# ElectricalLoads.net
KiCad netlist of a schematic drawn in EAGLE
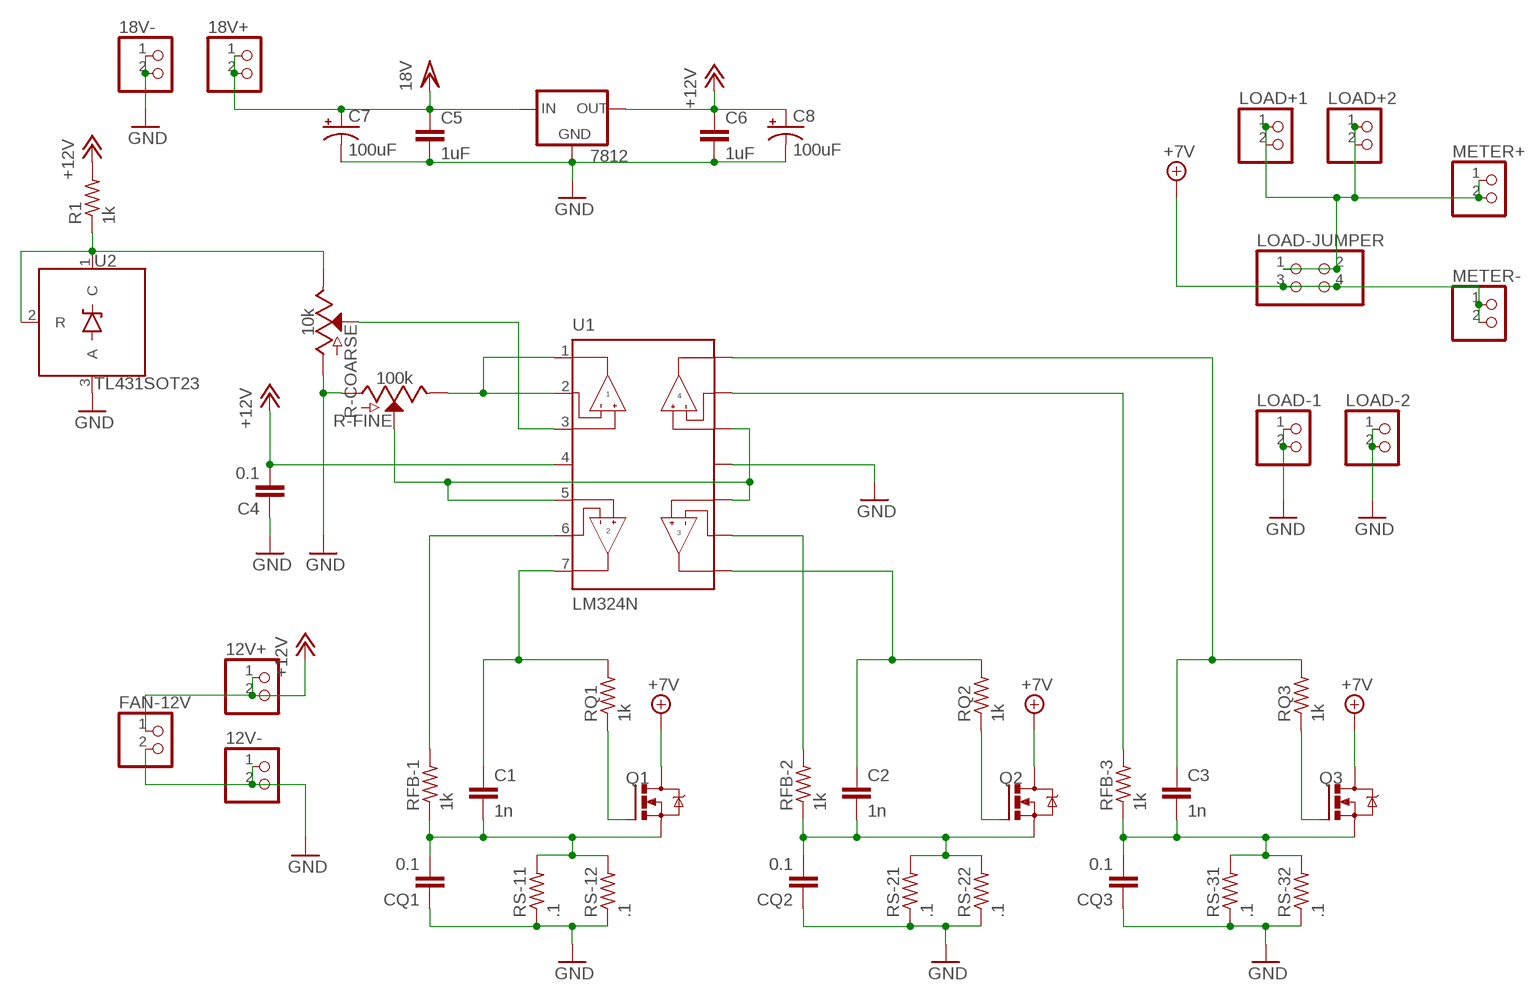
[diagram p0: schematic, sheet 1]

(export (version "E")
  (design (tool "Eeschema 10.0.6"))
  (components
    (comp (ref "12V+")
      (value "PINHD-1X2")
      (footprint "eagle-import:1X02")
      (libsource (lib "eagle-import") (part "PINHD-1X2"))
    )
    (comp (ref "12V-")
      (value "PINHD-1X2")
      (footprint "eagle-import:1X02")
      (libsource (lib "eagle-import") (part "PINHD-1X2"))
    )
    (comp (ref "18V+")
      (value "PINHD-1X2")
      (footprint "eagle-import:1X02")
      (libsource (lib "eagle-import") (part "PINHD-1X2"))
    )
    (comp (ref "18V-")
      (value "PINHD-1X2")
      (footprint "eagle-import:1X02")
      (libsource (lib "eagle-import") (part "PINHD-1X2"))
    )
    (comp (ref "7812")
      (value "V_REG_78XX-TO-220")
      (footprint "eagle-import:TO-220-ALT")
      (libsource (lib "eagle-import") (part "V_REG_78XX-TO-220"))
    )
    (comp (ref "C1")
      (value "1n")
      (footprint "eagle-import:0805")
      (libsource (lib "eagle-import") (part "CAP-0805"))
    )
    (comp (ref "C2")
      (value "1n")
      (footprint "eagle-import:0805")
      (libsource (lib "eagle-import") (part "CAP-0805"))
    )
    (comp (ref "C3")
      (value "1n")
      (footprint "eagle-import:0805")
      (libsource (lib "eagle-import") (part "CAP-0805"))
    )
    (comp (ref "C4")
      (value "0.1")
      (footprint "eagle-import:0805")
      (libsource (lib "eagle-import") (part "CAP-0805"))
    )
    (comp (ref "C5")
      (value "1uF")
      (footprint "eagle-import:1210")
      (libsource (lib "eagle-import") (part "10UF-1210-50V-20%"))
    )
    (comp (ref "C6")
      (value "1uF")
      (footprint "eagle-import:1210")
      (libsource (lib "eagle-import") (part "10UF-1210-50V-20%"))
    )
    (comp (ref "C7")
      (value "100uF")
      (footprint "eagle-import:PANASONIC_D")
      (libsource (lib "eagle-import") (part "100UF-POLAR-25V-20%(ELEC)"))
    )
    (comp (ref "C8")
      (value "100uF")
      (footprint "eagle-import:PANASONIC_D")
      (libsource (lib "eagle-import") (part "100UF-POLAR-25V-20%(ELEC)"))
    )
    (comp (ref "CQ1")
      (value "0.1")
      (footprint "eagle-import:0805")
      (libsource (lib "eagle-import") (part "CAP-0805"))
    )
    (comp (ref "CQ2")
      (value "0.1")
      (footprint "eagle-import:0805")
      (libsource (lib "eagle-import") (part "CAP-0805"))
    )
    (comp (ref "CQ3")
      (value "0.1")
      (footprint "eagle-import:0805")
      (libsource (lib "eagle-import") (part "CAP-0805"))
    )
    (comp (ref "FAN-12V")
      (value "PINHD-1X2")
      (footprint "eagle-import:1X02")
      (libsource (lib "eagle-import") (part "PINHD-1X2"))
    )
    (comp (ref "LOAD+1")
      (value "PINHD-1X2")
      (footprint "eagle-import:1X02")
      (libsource (lib "eagle-import") (part "PINHD-1X2"))
    )
    (comp (ref "LOAD+2")
      (value "PINHD-1X2")
      (footprint "eagle-import:1X02")
      (libsource (lib "eagle-import") (part "PINHD-1X2"))
    )
    (comp (ref "LOAD-1")
      (value "PINHD-1X2")
      (footprint "eagle-import:1X02")
      (libsource (lib "eagle-import") (part "PINHD-1X2"))
    )
    (comp (ref "LOAD-2")
      (value "PINHD-1X2")
      (footprint "eagle-import:1X02")
      (libsource (lib "eagle-import") (part "PINHD-1X2"))
    )
    (comp (ref "LOAD-JUMPER")
      (value "PINHD-2X2")
      (footprint "eagle-import:2X02")
      (libsource (lib "eagle-import") (part "PINHD-2X2"))
    )
    (comp (ref "METER+")
      (value "PINHD-1X2")
      (footprint "eagle-import:1X02")
      (libsource (lib "eagle-import") (part "PINHD-1X2"))
    )
    (comp (ref "METER-")
      (value "PINHD-1X2")
      (footprint "eagle-import:1X02")
      (libsource (lib "eagle-import") (part "PINHD-1X2"))
    )
    (comp (ref "Q1")
      (value "IRLZ44Z")
      (footprint "eagle-import:TO220BH")
      (libsource (lib "eagle-import") (part "IRLZ44Z"))
    )
    (comp (ref "Q2")
      (value "IRLZ44Z")
      (footprint "eagle-import:TO220BH")
      (libsource (lib "eagle-import") (part "IRLZ44Z"))
    )
    (comp (ref "Q3")
      (value "IRLZ44Z")
      (footprint "eagle-import:TO220BH")
      (libsource (lib "eagle-import") (part "IRLZ44Z"))
    )
    (comp (ref "R-COARSE")
      (value "10k")
      (footprint "eagle-import:POT-PTH-ALPS")
      (libsource (lib "eagle-import") (part "POTENTIOMETER-PTH-9MM-1/20W-20%"))
    )
    (comp (ref "R-FINE")
      (value "100k")
      (footprint "eagle-import:POT-PTH-ALPS")
      (libsource (lib "eagle-import") (part "POTENTIOMETER-PTH-9MM-1/20W-20%"))
    )
    (comp (ref "R1")
      (value "1k")
      (footprint "eagle-import:M0805")
      (libsource (lib "eagle-import") (part "R-US_M0805"))
    )
    (comp (ref "RFB-1")
      (value "1k")
      (footprint "eagle-import:M0805")
      (libsource (lib "eagle-import") (part "R-US_M0805"))
    )
    (comp (ref "RFB-2")
      (value "1k")
      (footprint "eagle-import:M0805")
      (libsource (lib "eagle-import") (part "R-US_M0805"))
    )
    (comp (ref "RFB-3")
      (value "1k")
      (footprint "eagle-import:M0805")
      (libsource (lib "eagle-import") (part "R-US_M0805"))
    )
    (comp (ref "RQ1")
      (value "1k")
      (footprint "eagle-import:M0805")
      (libsource (lib "eagle-import") (part "R-US_M0805"))
    )
    (comp (ref "RQ2")
      (value "1k")
      (footprint "eagle-import:M0805")
      (libsource (lib "eagle-import") (part "R-US_M0805"))
    )
    (comp (ref "RQ3")
      (value "1k")
      (footprint "eagle-import:M0805")
      (libsource (lib "eagle-import") (part "R-US_M0805"))
    )
    (comp (ref "RS-11")
      (value ".1")
      (footprint "eagle-import:M1206")
      (libsource (lib "eagle-import") (part "R-US_M1206"))
    )
    (comp (ref "RS-12")
      (value ".1")
      (footprint "eagle-import:M1206")
      (libsource (lib "eagle-import") (part "R-US_M1206"))
    )
    (comp (ref "RS-21")
      (value ".1")
      (footprint "eagle-import:M1206")
      (libsource (lib "eagle-import") (part "R-US_M1206"))
    )
    (comp (ref "RS-22")
      (value ".1")
      (footprint "eagle-import:M1206")
      (libsource (lib "eagle-import") (part "R-US_M1206"))
    )
    (comp (ref "RS-31")
      (value ".1")
      (footprint "eagle-import:M1206")
      (libsource (lib "eagle-import") (part "R-US_M1206"))
    )
    (comp (ref "RS-32")
      (value ".1")
      (footprint "eagle-import:M1206")
      (libsource (lib "eagle-import") (part "R-US_M1206"))
    )
    (comp (ref "U1")
      (value "LM324N")
      (footprint "eagle-import:DIP762W45P254L1969H508Q14")
      (fields (field (name "MF") "Texas Instruments"))
      (libsource (lib "eagle-import") (part "LM324N"))
    )
    (comp (ref "U2")
      (value "TL431SOT23")
      (footprint "eagle-import:SOT23-3")
      (libsource (lib "eagle-import") (part "TL431SOT23"))
    )
  )
  (nets
    (net (code "1") (name "+7V") (class "Default")
      (node (ref "LOAD-JUMPER") (pin "3") (pinfunction "3_3") (pintype "passive"))
      (node (ref "LOAD-JUMPER") (pin "4") (pinfunction "4_4") (pintype "passive"))
      (node (ref "METER-") (pin "1") (pinfunction "1_1") (pintype "passive"))
      (node (ref "METER-") (pin "2") (pinfunction "2_2") (pintype "passive"))
      (node (ref "Q1") (pin "D") (pinfunction "D_D") (pintype "passive"))
      (node (ref "Q2") (pin "D") (pinfunction "D_D") (pintype "passive"))
      (node (ref "Q3") (pin "D") (pinfunction "D_D") (pintype "passive"))
    )
    (net (code "2") (name "+12V") (class "Default")
      (node (ref "12V+") (pin "1") (pinfunction "1_1") (pintype "passive"))
      (node (ref "12V+") (pin "2") (pinfunction "2_2") (pintype "passive"))
      (node (ref "7812") (pin "OUT") (pinfunction "OUT_OUT") (pintype "passive"))
      (node (ref "C4") (pin "2") (pinfunction "2_2") (pintype "passive"))
      (node (ref "C6") (pin "1") (pinfunction "1_1") (pintype "passive"))
      (node (ref "C8") (pin "+") (pinfunction "+_+") (pintype "passive"))
      (node (ref "FAN-12V") (pin "1") (pinfunction "1_1") (pintype "passive"))
      (node (ref "R1") (pin "2") (pinfunction "2_2") (pintype "passive"))
      (node (ref "U1") (pin "4") (pinfunction "VCC_4") (pintype "power_in"))
    )
    (net (code "3") (name "18V") (class "Default")
      (node (ref "18V+") (pin "1") (pinfunction "1_1") (pintype "passive"))
      (node (ref "18V+") (pin "2") (pinfunction "2_2") (pintype "passive"))
      (node (ref "7812") (pin "IN") (pinfunction "IN_IN") (pintype "input"))
      (node (ref "C5") (pin "1") (pinfunction "1_1") (pintype "passive"))
      (node (ref "C7") (pin "+") (pinfunction "+_+") (pintype "passive"))
    )
    (net (code "4") (name "GND") (class "Default")
      (node (ref "12V-") (pin "1") (pinfunction "1_1") (pintype "passive"))
      (node (ref "12V-") (pin "2") (pinfunction "2_2") (pintype "passive"))
      (node (ref "18V-") (pin "1") (pinfunction "1_1") (pintype "passive"))
      (node (ref "18V-") (pin "2") (pinfunction "2_2") (pintype "passive"))
      (node (ref "7812") (pin "GND") (pinfunction "GND_GND") (pintype "input"))
      (node (ref "C4") (pin "1") (pinfunction "1_1") (pintype "passive"))
      (node (ref "C5") (pin "2") (pinfunction "2_2") (pintype "passive"))
      (node (ref "C6") (pin "2") (pinfunction "2_2") (pintype "passive"))
      (node (ref "C7") (pin "-") (pinfunction "-_-") (pintype "passive"))
      (node (ref "C8") (pin "-") (pinfunction "-_-") (pintype "passive"))
      (node (ref "CQ1") (pin "1") (pinfunction "1_1") (pintype "passive"))
      (node (ref "CQ2") (pin "1") (pinfunction "1_1") (pintype "passive"))
      (node (ref "CQ3") (pin "1") (pinfunction "1_1") (pintype "passive"))
      (node (ref "FAN-12V") (pin "2") (pinfunction "2_2") (pintype "passive"))
      (node (ref "LOAD-1") (pin "1") (pinfunction "1_1") (pintype "passive"))
      (node (ref "LOAD-1") (pin "2") (pinfunction "2_2") (pintype "passive"))
      (node (ref "LOAD-2") (pin "1") (pinfunction "1_1") (pintype "passive"))
      (node (ref "LOAD-2") (pin "2") (pinfunction "2_2") (pintype "passive"))
      (node (ref "R-COARSE") (pin "P$3") (pinfunction "A_P$3") (pintype "passive"))
      (node (ref "R-FINE") (pin "P$3") (pinfunction "A_P$3") (pintype "passive"))
      (node (ref "RS-11") (pin "1") (pinfunction "1_1") (pintype "passive"))
      (node (ref "RS-12") (pin "1") (pinfunction "1_1") (pintype "passive"))
      (node (ref "RS-21") (pin "1") (pinfunction "1_1") (pintype "passive"))
      (node (ref "RS-22") (pin "1") (pinfunction "1_1") (pintype "passive"))
      (node (ref "RS-31") (pin "1") (pinfunction "1_1") (pintype "passive"))
      (node (ref "RS-32") (pin "1") (pinfunction "1_1") (pintype "passive"))
      (node (ref "U1") (pin "11") (pinfunction "GND_11") (pintype "power_in"))
      (node (ref "U2") (pin "3") (pinfunction "A_3") (pintype "bidirectional"))
    )
    (net (code "5") (name "Net-(C1-Pad2)") (class "Default")
      (node (ref "C1") (pin "2") (pinfunction "2_2") (pintype "passive"))
      (node (ref "CQ1") (pin "2") (pinfunction "2_2") (pintype "passive"))
      (node (ref "Q1") (pin "S") (pinfunction "S_S") (pintype "passive"))
      (node (ref "RFB-1") (pin "1") (pinfunction "1_1") (pintype "passive"))
      (node (ref "RS-11") (pin "2") (pinfunction "2_2") (pintype "passive"))
      (node (ref "RS-12") (pin "2") (pinfunction "2_2") (pintype "passive"))
    )
    (net (code "6") (name "Net-(C2-Pad2)") (class "Default")
      (node (ref "C2") (pin "2") (pinfunction "2_2") (pintype "passive"))
      (node (ref "CQ2") (pin "2") (pinfunction "2_2") (pintype "passive"))
      (node (ref "Q2") (pin "S") (pinfunction "S_S") (pintype "passive"))
      (node (ref "RFB-2") (pin "1") (pinfunction "1_1") (pintype "passive"))
      (node (ref "RS-21") (pin "2") (pinfunction "2_2") (pintype "passive"))
      (node (ref "RS-22") (pin "2") (pinfunction "2_2") (pintype "passive"))
    )
    (net (code "7") (name "Net-(C3-Pad2)") (class "Default")
      (node (ref "C3") (pin "2") (pinfunction "2_2") (pintype "passive"))
      (node (ref "CQ3") (pin "2") (pinfunction "2_2") (pintype "passive"))
      (node (ref "Q3") (pin "S") (pinfunction "S_S") (pintype "passive"))
      (node (ref "RFB-3") (pin "1") (pinfunction "1_1") (pintype "passive"))
      (node (ref "RS-31") (pin "2") (pinfunction "2_2") (pintype "passive"))
      (node (ref "RS-32") (pin "2") (pinfunction "2_2") (pintype "passive"))
    )
    (net (code "8") (name "Net-(LOAD+1-Pad1)") (class "Default")
      (node (ref "LOAD+1") (pin "1") (pinfunction "1_1") (pintype "passive"))
      (node (ref "LOAD+1") (pin "2") (pinfunction "2_2") (pintype "passive"))
      (node (ref "LOAD+2") (pin "1") (pinfunction "1_1") (pintype "passive"))
      (node (ref "LOAD+2") (pin "2") (pinfunction "2_2") (pintype "passive"))
      (node (ref "LOAD-JUMPER") (pin "1") (pinfunction "1_1") (pintype "passive"))
      (node (ref "LOAD-JUMPER") (pin "2") (pinfunction "2_2") (pintype "passive"))
      (node (ref "METER+") (pin "1") (pinfunction "1_1") (pintype "passive"))
      (node (ref "METER+") (pin "2") (pinfunction "2_2") (pintype "passive"))
    )
    (net (code "9") (name "Net-(Q1-PadG)") (class "Default")
      (node (ref "Q1") (pin "G") (pinfunction "G_G") (pintype "passive"))
      (node (ref "RQ1") (pin "1") (pinfunction "1_1") (pintype "passive"))
    )
    (net (code "10") (name "Net-(Q2-PadG)") (class "Default")
      (node (ref "Q2") (pin "G") (pinfunction "G_G") (pintype "passive"))
      (node (ref "RQ2") (pin "1") (pinfunction "1_1") (pintype "passive"))
    )
    (net (code "11") (name "Net-(Q3-PadG)") (class "Default")
      (node (ref "Q3") (pin "G") (pinfunction "G_G") (pintype "passive"))
      (node (ref "RQ3") (pin "1") (pinfunction "1_1") (pintype "passive"))
    )
    (net (code "12") (name "Net-(R-COARSE-E)") (class "Default")
      (node (ref "R-COARSE") (pin "P$1") (pinfunction "E_P$1") (pintype "passive"))
      (node (ref "R1") (pin "1") (pinfunction "1_1") (pintype "passive"))
      (node (ref "U2") (pin "1") (pinfunction "C_1") (pintype "bidirectional"))
      (node (ref "U2") (pin "2") (pinfunction "R_2") (pintype "bidirectional"))
    )
    (net (code "13") (name "Net-(R-COARSE-S)") (class "Default")
      (node (ref "R-COARSE") (pin "P$2") (pinfunction "S_P$2") (pintype "passive"))
      (node (ref "U1") (pin "3") (pinfunction "1IN+_3") (pintype "input"))
    )
    (net (code "14") (name "Net-(R-FINE-E)") (class "Default")
      (node (ref "R-FINE") (pin "P$1") (pinfunction "E_P$1") (pintype "passive"))
      (node (ref "U1") (pin "1") (pinfunction "1OUT_1") (pintype "output"))
      (node (ref "U1") (pin "2") (pinfunction "1IN-_2") (pintype "input"))
    )
    (net (code "15") (name "Net-(R-FINE-S)") (class "Default")
      (node (ref "R-FINE") (pin "P$2") (pinfunction "S_P$2") (pintype "passive"))
      (node (ref "U1") (pin "10") (pinfunction "3IN+_10") (pintype "input"))
      (node (ref "U1") (pin "12") (pinfunction "4IN+_12") (pintype "input"))
      (node (ref "U1") (pin "5") (pinfunction "2IN+_5") (pintype "input"))
    )
    (net (code "16") (name "Net-(U1-2IN-)") (class "Default")
      (node (ref "RFB-1") (pin "2") (pinfunction "2_2") (pintype "passive"))
      (node (ref "U1") (pin "6") (pinfunction "2IN-_6") (pintype "input"))
    )
    (net (code "17") (name "Net-(U1-2OUT)") (class "Default")
      (node (ref "C1") (pin "1") (pinfunction "1_1") (pintype "passive"))
      (node (ref "RQ1") (pin "2") (pinfunction "2_2") (pintype "passive"))
      (node (ref "U1") (pin "7") (pinfunction "2OUT_7") (pintype "output"))
    )
    (net (code "18") (name "Net-(U1-3IN-)") (class "Default")
      (node (ref "RFB-2") (pin "2") (pinfunction "2_2") (pintype "passive"))
      (node (ref "U1") (pin "9") (pinfunction "3IN-_9") (pintype "input"))
    )
    (net (code "19") (name "Net-(U1-3OUT)") (class "Default")
      (node (ref "C2") (pin "1") (pinfunction "1_1") (pintype "passive"))
      (node (ref "RQ2") (pin "2") (pinfunction "2_2") (pintype "passive"))
      (node (ref "U1") (pin "8") (pinfunction "3OUT_8") (pintype "output"))
    )
    (net (code "20") (name "Net-(U1-4IN-)") (class "Default")
      (node (ref "RFB-3") (pin "2") (pinfunction "2_2") (pintype "passive"))
      (node (ref "U1") (pin "13") (pinfunction "4IN-_13") (pintype "input"))
    )
    (net (code "21") (name "Net-(U1-4OUT)") (class "Default")
      (node (ref "C3") (pin "1") (pinfunction "1_1") (pintype "passive"))
      (node (ref "RQ3") (pin "2") (pinfunction "2_2") (pintype "passive"))
      (node (ref "U1") (pin "14") (pinfunction "4OUT_14") (pintype "output"))
    )
  )
)
